# LPCB278_-_RM57_LAUNCH.net
KiCad netlist of a schematic drawn in Altium Designer
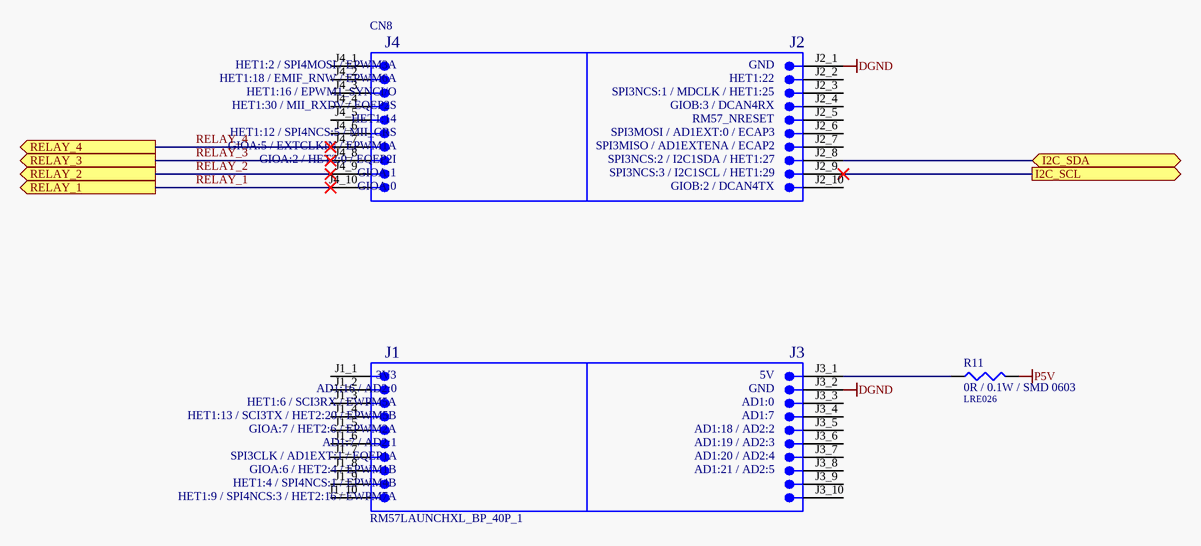
[diagram p0: LPCB278 - RM57 LAUNCH.SchDoc]

(export (version "E")
  (design (tool "Eeschema 10.0.6"))
  (components
    (comp (ref "CN8")
      (value "RM57LAUNCHXL_BP_40P_1")
      (footprint "RM57LAUNCHXL_BP_40P_1")
      (description "Connector, RM57L843 LaunchXL, 40Pin Boosterpack Site1")
      (libsource (lib "LDL_Connectors") (part "RM57LAUNCHXL_BP_40P_1"))
    )
    (comp (ref "R11")
      (value "0R / 0.1W / SMD 0603")
      (footprint "LFP020__CR1608-0603-IPC7351_B")
      (description "Resistor, Ceramic Chip, 0R, 0.1W, SMD 0603 [LRE026]")
      (fields (field (name "LDL_NUMBER") "LRE026"))
      (libsource (lib "LDL_Resistors") (part "0R / 0.1W / SMD 0603"))
    )
  )
  (nets
    (net (code "1") (name "/I2C_SCL") (class "Default")
      (node (ref "CN8") (pin "J2_9") (pintype "passive+no_connect"))
    )
    (net (code "2") (name "/I2C_SDA") (class "Default") (node (ref "CN8") (pin "J2_8") (pintype "passive")))
    (net (code "3") (name "/RELAY_1") (class "Default")
      (node (ref "CN8") (pin "J4_10") (pintype "passive+no_connect"))
    )
    (net (code "4") (name "/RELAY_2") (class "Default")
      (node (ref "CN8") (pin "J4_9") (pintype "passive+no_connect"))
    )
    (net (code "5") (name "/RELAY_3") (class "Default")
      (node (ref "CN8") (pin "J4_8") (pintype "passive+no_connect"))
    )
    (net (code "6") (name "/RELAY_4") (class "Default")
      (node (ref "CN8") (pin "J4_7") (pintype "passive+no_connect"))
    )
    (net (code "7") (name "DGND") (class "Default")
      (node (ref "CN8") (pin "J2_1") (pintype "passive"))
      (node (ref "CN8") (pin "J3_2") (pintype "passive"))
    )
    (net (code "8") (name "Net-(CN8-PadJ3_1)") (class "Default")
      (node (ref "CN8") (pin "J3_1") (pintype "passive"))
      (node (ref "R11") (pin "1") (pintype "passive"))
    )
    (net (code "9") (name "P5V") (class "Default") (node (ref "R11") (pin "2") (pintype "passive")))
    (net (code "10") (name "unconnected-(CN8-PadJ1_1)") (class "Default")
      (node (ref "CN8") (pin "J1_1") (pintype "passive"))
    )
    (net (code "11") (name "unconnected-(CN8-PadJ1_2)") (class "Default")
      (node (ref "CN8") (pin "J1_2") (pintype "passive"))
    )
    (net (code "12") (name "unconnected-(CN8-PadJ1_3)") (class "Default")
      (node (ref "CN8") (pin "J1_3") (pintype "passive"))
    )
    (net (code "13") (name "unconnected-(CN8-PadJ1_4)") (class "Default")
      (node (ref "CN8") (pin "J1_4") (pintype "passive"))
    )
    (net (code "14") (name "unconnected-(CN8-PadJ1_5)") (class "Default")
      (node (ref "CN8") (pin "J1_5") (pintype "passive"))
    )
    (net (code "15") (name "unconnected-(CN8-PadJ1_6)") (class "Default")
      (node (ref "CN8") (pin "J1_6") (pintype "passive"))
    )
    (net (code "16") (name "unconnected-(CN8-PadJ1_7)") (class "Default")
      (node (ref "CN8") (pin "J1_7") (pintype "passive"))
    )
    (net (code "17") (name "unconnected-(CN8-PadJ1_8)") (class "Default")
      (node (ref "CN8") (pin "J1_8") (pintype "passive"))
    )
    (net (code "18") (name "unconnected-(CN8-PadJ1_9)") (class "Default")
      (node (ref "CN8") (pin "J1_9") (pintype "passive"))
    )
    (net (code "19") (name "unconnected-(CN8-PadJ1_10)") (class "Default")
      (node (ref "CN8") (pin "J1_10") (pintype "passive"))
    )
    (net (code "20") (name "unconnected-(CN8-PadJ2_2)") (class "Default")
      (node (ref "CN8") (pin "J2_2") (pintype "passive"))
    )
    (net (code "21") (name "unconnected-(CN8-PadJ2_3)") (class "Default")
      (node (ref "CN8") (pin "J2_3") (pintype "passive"))
    )
    (net (code "22") (name "unconnected-(CN8-PadJ2_4)") (class "Default")
      (node (ref "CN8") (pin "J2_4") (pintype "passive"))
    )
    (net (code "23") (name "unconnected-(CN8-PadJ2_5)") (class "Default")
      (node (ref "CN8") (pin "J2_5") (pintype "passive"))
    )
    (net (code "24") (name "unconnected-(CN8-PadJ2_6)") (class "Default")
      (node (ref "CN8") (pin "J2_6") (pintype "passive"))
    )
    (net (code "25") (name "unconnected-(CN8-PadJ2_7)") (class "Default")
      (node (ref "CN8") (pin "J2_7") (pintype "passive"))
    )
    (net (code "26") (name "unconnected-(CN8-PadJ2_10)") (class "Default")
      (node (ref "CN8") (pin "J2_10") (pintype "passive"))
    )
    (net (code "27") (name "unconnected-(CN8-PadJ3_3)") (class "Default")
      (node (ref "CN8") (pin "J3_3") (pintype "passive"))
    )
    (net (code "28") (name "unconnected-(CN8-PadJ3_4)") (class "Default")
      (node (ref "CN8") (pin "J3_4") (pintype "passive"))
    )
    (net (code "29") (name "unconnected-(CN8-PadJ3_5)") (class "Default")
      (node (ref "CN8") (pin "J3_5") (pintype "passive"))
    )
    (net (code "30") (name "unconnected-(CN8-PadJ3_6)") (class "Default")
      (node (ref "CN8") (pin "J3_6") (pintype "passive"))
    )
    (net (code "31") (name "unconnected-(CN8-PadJ3_7)") (class "Default")
      (node (ref "CN8") (pin "J3_7") (pintype "passive"))
    )
    (net (code "32") (name "unconnected-(CN8-PadJ3_8)") (class "Default")
      (node (ref "CN8") (pin "J3_8") (pintype "passive"))
    )
    (net (code "33") (name "unconnected-(CN8-PadJ3_9)") (class "Default")
      (node (ref "CN8") (pin "J3_9") (pintype "passive"))
    )
    (net (code "34") (name "unconnected-(CN8-PadJ3_10)") (class "Default")
      (node (ref "CN8") (pin "J3_10") (pintype "passive"))
    )
    (net (code "35") (name "unconnected-(CN8-PadJ4_1)") (class "Default")
      (node (ref "CN8") (pin "J4_1") (pintype "passive"))
    )
    (net (code "36") (name "unconnected-(CN8-PadJ4_2)") (class "Default")
      (node (ref "CN8") (pin "J4_2") (pintype "passive"))
    )
    (net (code "37") (name "unconnected-(CN8-PadJ4_3)") (class "Default")
      (node (ref "CN8") (pin "J4_3") (pintype "passive"))
    )
    (net (code "38") (name "unconnected-(CN8-PadJ4_4)") (class "Default")
      (node (ref "CN8") (pin "J4_4") (pintype "passive"))
    )
    (net (code "39") (name "unconnected-(CN8-PadJ4_5)") (class "Default")
      (node (ref "CN8") (pin "J4_5") (pintype "passive"))
    )
    (net (code "40") (name "unconnected-(CN8-PadJ4_6)") (class "Default")
      (node (ref "CN8") (pin "J4_6") (pintype "passive"))
    )
  )
)
